# Arduino_UNO_blank_shield.net
KiCad netlist of a schematic drawn in EAGLE
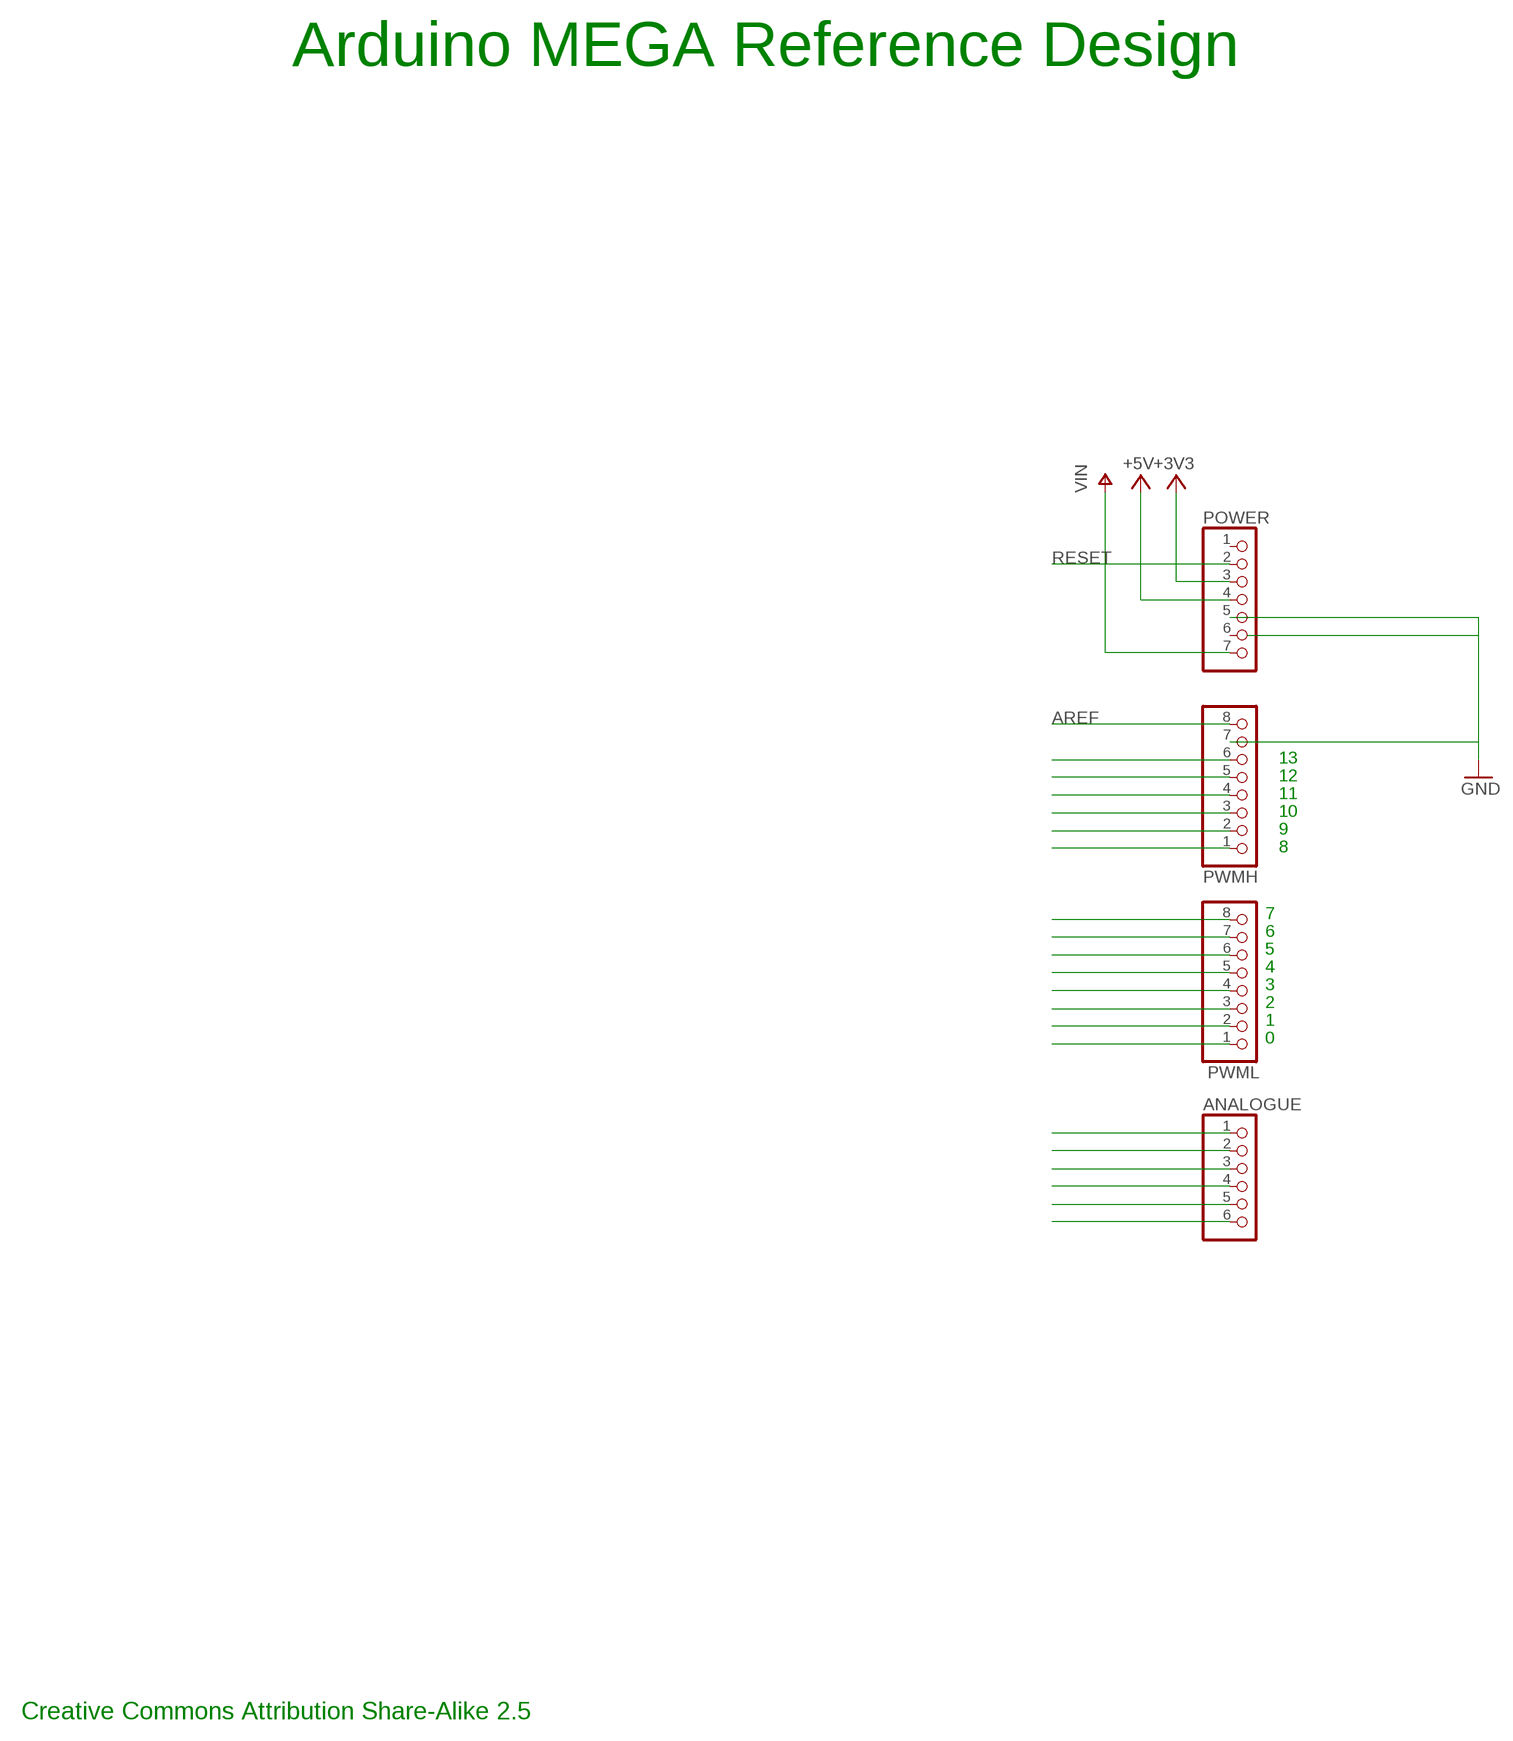
[diagram p0: schematic, sheet 1]

(export (version "E")
  (design (tool "Eeschema 10.0.6"))
  (components
    (comp (ref "ANALOGUE")
      (value "PINHD-1X6")
      (footprint "eagle-import:1X06")
      (libsource (lib "eagle-import") (part "PINHD-1X6"))
    )
    (comp (ref "POWER")
      (value "PINHD-1X7")
      (footprint "eagle-import:1X07")
      (libsource (lib "eagle-import") (part "PINHD-1X7"))
    )
    (comp (ref "PWMH")
      (value "PINHD-1X8")
      (footprint "eagle-import:1X08")
      (libsource (lib "eagle-import") (part "PINHD-1X8"))
    )
    (comp (ref "PWML")
      (value "PINHD-1X8")
      (footprint "eagle-import:1X08")
      (libsource (lib "eagle-import") (part "PINHD-1X8"))
    )
  )
  (nets
    (net (code "1") (name "+3V3") (class "Default")
      (node (ref "POWER") (pin "3") (pinfunction "3_3") (pintype "passive"))
    )
    (net (code "2") (name "+5V") (class "Default")
      (node (ref "POWER") (pin "4") (pinfunction "4_4") (pintype "passive"))
    )
    (net (code "3") (name "/AREF") (class "Default")
      (node (ref "PWMH") (pin "8") (pinfunction "8_8") (pintype "passive"))
    )
    (net (code "4") (name "/RESET") (class "Default")
      (node (ref "POWER") (pin "2") (pinfunction "2_2") (pintype "passive"))
    )
    (net (code "5") (name "GND") (class "Default")
      (node (ref "POWER") (pin "5") (pinfunction "5_5") (pintype "passive"))
      (node (ref "PWMH") (pin "7") (pinfunction "7_7") (pintype "passive"))
    )
    (net (code "6") (name "VIN") (class "Default")
      (node (ref "POWER") (pin "7") (pinfunction "7_7") (pintype "passive"))
    )
    (net (code "7") (name "unconnected-(ANALOGUE-Pad1)") (class "Default")
      (node (ref "ANALOGUE") (pin "1") (pinfunction "1_1") (pintype "passive"))
    )
    (net (code "8") (name "unconnected-(ANALOGUE-Pad2)") (class "Default")
      (node (ref "ANALOGUE") (pin "2") (pinfunction "2_2") (pintype "passive"))
    )
    (net (code "9") (name "unconnected-(ANALOGUE-Pad3)") (class "Default")
      (node (ref "ANALOGUE") (pin "3") (pinfunction "3_3") (pintype "passive"))
    )
    (net (code "10") (name "unconnected-(ANALOGUE-Pad4)") (class "Default")
      (node (ref "ANALOGUE") (pin "4") (pinfunction "4_4") (pintype "passive"))
    )
    (net (code "11") (name "unconnected-(ANALOGUE-Pad5)") (class "Default")
      (node (ref "ANALOGUE") (pin "5") (pinfunction "5_5") (pintype "passive"))
    )
    (net (code "12") (name "unconnected-(ANALOGUE-Pad6)") (class "Default")
      (node (ref "ANALOGUE") (pin "6") (pinfunction "6_6") (pintype "passive"))
    )
    (net (code "13") (name "unconnected-(POWER-Pad1)") (class "Default")
      (node (ref "POWER") (pin "1") (pinfunction "1_1") (pintype "passive"))
    )
    (net (code "14") (name "unconnected-(POWER-Pad6)") (class "Default")
      (node (ref "POWER") (pin "6") (pinfunction "6_6") (pintype "passive"))
    )
    (net (code "15") (name "unconnected-(PWMH-Pad1)") (class "Default")
      (node (ref "PWMH") (pin "1") (pinfunction "1_1") (pintype "passive"))
    )
    (net (code "16") (name "unconnected-(PWMH-Pad2)") (class "Default")
      (node (ref "PWMH") (pin "2") (pinfunction "2_2") (pintype "passive"))
    )
    (net (code "17") (name "unconnected-(PWMH-Pad3)") (class "Default")
      (node (ref "PWMH") (pin "3") (pinfunction "3_3") (pintype "passive"))
    )
    (net (code "18") (name "unconnected-(PWMH-Pad4)") (class "Default")
      (node (ref "PWMH") (pin "4") (pinfunction "4_4") (pintype "passive"))
    )
    (net (code "19") (name "unconnected-(PWMH-Pad5)") (class "Default")
      (node (ref "PWMH") (pin "5") (pinfunction "5_5") (pintype "passive"))
    )
    (net (code "20") (name "unconnected-(PWMH-Pad6)") (class "Default")
      (node (ref "PWMH") (pin "6") (pinfunction "6_6") (pintype "passive"))
    )
    (net (code "21") (name "unconnected-(PWML-Pad1)") (class "Default")
      (node (ref "PWML") (pin "1") (pinfunction "1_1") (pintype "passive"))
    )
    (net (code "22") (name "unconnected-(PWML-Pad2)") (class "Default")
      (node (ref "PWML") (pin "2") (pinfunction "2_2") (pintype "passive"))
    )
    (net (code "23") (name "unconnected-(PWML-Pad3)") (class "Default")
      (node (ref "PWML") (pin "3") (pinfunction "3_3") (pintype "passive"))
    )
    (net (code "24") (name "unconnected-(PWML-Pad4)") (class "Default")
      (node (ref "PWML") (pin "4") (pinfunction "4_4") (pintype "passive"))
    )
    (net (code "25") (name "unconnected-(PWML-Pad5)") (class "Default")
      (node (ref "PWML") (pin "5") (pinfunction "5_5") (pintype "passive"))
    )
    (net (code "26") (name "unconnected-(PWML-Pad6)") (class "Default")
      (node (ref "PWML") (pin "6") (pinfunction "6_6") (pintype "passive"))
    )
    (net (code "27") (name "unconnected-(PWML-Pad7)") (class "Default")
      (node (ref "PWML") (pin "7") (pinfunction "7_7") (pintype "passive"))
    )
    (net (code "28") (name "unconnected-(PWML-Pad8)") (class "Default")
      (node (ref "PWML") (pin "8") (pinfunction "8_8") (pintype "passive"))
    )
  )
)
